# USB_UART.net
KiCad netlist of a schematic drawn in Altium Designer
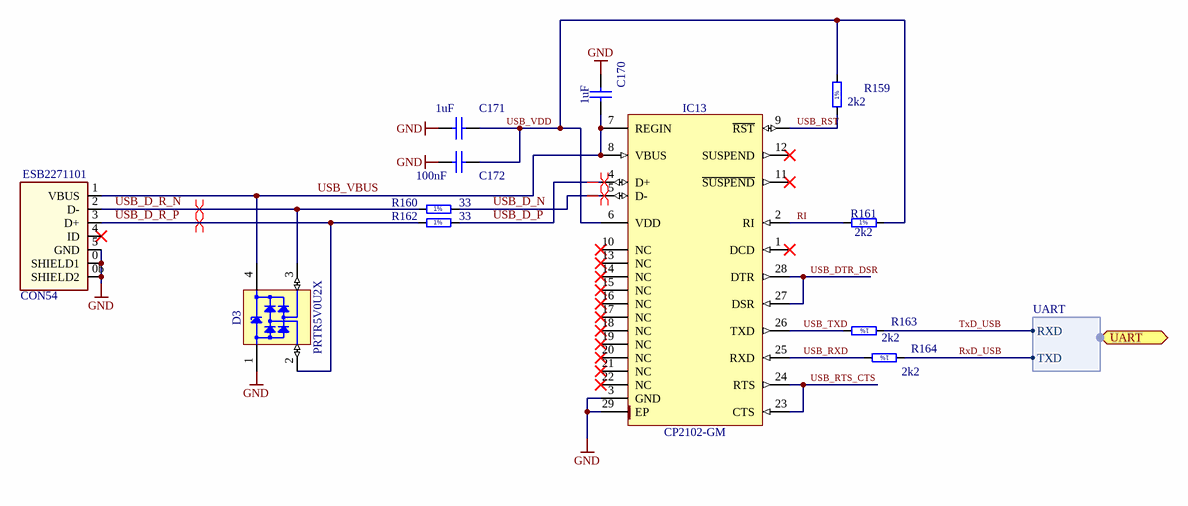
[diagram p0: USB_UART.SchDoc]

(export (version "E")
  (design (tool "Eeschema 10.0.6"))
  (components
    (comp (ref "C170")
      (value "1uF")
      (footprint "CAPC1608X87N")
      (description "Non-polarised capacitor")
      (fields
        (field (name "PART NUMBER") "CC0603_1UF_16V_10%_X7R")
        (field (name "VOLTAGE") "16V")
        (field (name "AUTHOR") "CERN DEM JLC")
      )
      (libsource (lib "Capacitors") (part "Capacitor - non polarized"))
    )
    (comp (ref "C171")
      (value "1uF")
      (footprint "CAPC1608X87N")
      (description "Non-polarised capacitor")
      (fields
        (field (name "PART NUMBER") "CC0603_1UF_16V_10%_X7R")
        (field (name "VOLTAGE") "16V")
        (field (name "AUTHOR") "CERN DEM JLC")
      )
      (libsource (lib "Capacitors") (part "Capacitor - non polarized"))
    )
    (comp (ref "C172")
      (value "100nF")
      (footprint "CAPC0603X33N")
      (description "Non-polarised capacitor")
      (fields
        (field (name "PART NUMBER") "CC0201_100NF_6.3V_10%_X5R")
        (field (name "VOLTAGE") "6.3V")
        (field (name "AUTHOR") "CERN DEM JLC")
      )
      (libsource (lib "Capacitors") (part "Capacitor - non polarized"))
    )
    (comp (ref "CON54")
      (value "ESB2271101")
      (footprint "USB_MICRO_ESB2271101")
      (description "USB micro AB connector")
      (fields (field (name "PART NUMBER") "10133"))
      (libsource (lib "LIBRARY_SCH") (part "CON_USB_AB_MICRO"))
    )
    (comp (ref "D3")
      (value "PRTR5V0U2X")
      (footprint "SOT190P230X110-4N")
      (description "Ultra Low Capacitance Double Rail-to-Rail ESD Protection Diode")
      (fields
        (field (name "VOLTAGE") "5.5V")
        (field (name "MANUFACTURER") "NXP SEMICONDUCTORS")
        (field (name "AUTHOR") "CERN DEM JLC")
      )
      (libsource (lib "ICs And Semiconductors") (part "PRTR5V0U2X"))
    )
    (comp (ref "IC13")
      (value "CP2102-GM")
      (footprint "QFN50P500X500X100-29N-S335")
      (description "Single-Chip USB to UART Bridge")
      (fields (field (name "MANUFACTURER") "SILICON LABS") (field (name "AUTHOR") "CERN DEM JLC"))
      (libsource (lib "ICs And Semiconductors") (part "CP2102-GM"))
    )
    (comp (ref "R159")
      (value "2k2")
      (footprint "RESC1005X40N")
      (description "Resistor - 1%")
      (fields
        (field (name "PART NUMBER") "R0402_2K2_1%_0.0625W_100PPM")
        (field (name "POWER") "0.0625W")
        (field (name "AUTHOR") "CERN DEM JLC")
      )
      (libsource (lib "Resistors") (part "Resistor - 1%"))
    )
    (comp (ref "R160")
      (value "33")
      (footprint "RESC1005X40N")
      (description "Resistor - 1%")
      (fields
        (field (name "PART NUMBER") "R0402_33R_1%_0.0625W_100PPM")
        (field (name "POWER") "0.0625W")
        (field (name "AUTHOR") "CERN DEM JLC")
      )
      (libsource (lib "Resistors") (part "Resistor - 1%"))
    )
    (comp (ref "R161")
      (value "2k2")
      (footprint "RESC1005X40N")
      (description "Resistor - 1%")
      (fields
        (field (name "PART NUMBER") "R0402_2K2_1%_0.0625W_100PPM")
        (field (name "POWER") "0.0625W")
        (field (name "AUTHOR") "CERN DEM JLC")
      )
      (libsource (lib "Resistors") (part "Resistor - 1%"))
    )
    (comp (ref "R162")
      (value "33")
      (footprint "RESC1005X40N")
      (description "Resistor - 1%")
      (fields
        (field (name "PART NUMBER") "R0402_33R_1%_0.0625W_100PPM")
        (field (name "POWER") "0.0625W")
        (field (name "AUTHOR") "CERN DEM JLC")
      )
      (libsource (lib "Resistors") (part "Resistor - 1%"))
    )
    (comp (ref "R163")
      (value "2k2")
      (footprint "RESC1005X40N")
      (description "Resistor - 1%")
      (fields
        (field (name "PART NUMBER") "R0402_2K2_1%_0.0625W_100PPM")
        (field (name "POWER") "0.0625W")
        (field (name "AUTHOR") "CERN DEM JLC")
      )
      (libsource (lib "Resistors") (part "Resistor - 1%"))
    )
    (comp (ref "R164")
      (value "2k2")
      (footprint "RESC1005X40N")
      (description "Resistor - 1%")
      (fields
        (field (name "PART NUMBER") "R0402_2K2_1%_0.0625W_100PPM")
        (field (name "POWER") "0.0625W")
        (field (name "AUTHOR") "CERN DEM JLC")
      )
      (libsource (lib "Resistors") (part "Resistor - 1%"))
    )
  )
  (nets
    (net (code "2") (name "/RI") (class "Default")
      (node (ref "IC13") (pin "2") (pinfunction "RI_2") (pintype "input"))
      (node (ref "R161") (pin "1") (pinfunction "1_1") (pintype "passive"))
    )
    (net (code "3") (name "/RxD_USB") (class "Default")
      (node (ref "R164") (pin "1") (pinfunction "1_1") (pintype "passive"))
    )
    (net (code "4") (name "/TxD_USB") (class "Default")
      (node (ref "R163") (pin "1") (pinfunction "1_1") (pintype "passive"))
    )
    (net (code "5") (name "/USB_DTR_DSR") (class "Default")
      (node (ref "IC13") (pin "27") (pinfunction "DSR_27") (pintype "input"))
      (node (ref "IC13") (pin "28") (pinfunction "DTR_28") (pintype "output"))
    )
    (net (code "6") (name "/USB_D_N") (class "Default")
      (node (ref "IC13") (pin "5") (pinfunction "D-_5") (pintype "bidirectional"))
      (node (ref "R160") (pin "2") (pinfunction "2_2") (pintype "passive"))
    )
    (net (code "7") (name "/USB_D_P") (class "Default")
      (node (ref "IC13") (pin "4") (pinfunction "D+_4") (pintype "bidirectional"))
      (node (ref "R162") (pin "2") (pinfunction "2_2") (pintype "passive"))
    )
    (net (code "8") (name "/USB_D_R_N") (class "Default")
      (node (ref "CON54") (pin "2") (pinfunction "D-_2") (pintype "passive"))
      (node (ref "D3") (pin "3") (pinfunction "I/O2_3") (pintype "bidirectional"))
      (node (ref "R160") (pin "1") (pinfunction "1_1") (pintype "passive"))
    )
    (net (code "9") (name "/USB_D_R_P") (class "Default")
      (node (ref "CON54") (pin "3") (pinfunction "D+_3") (pintype "passive"))
      (node (ref "D3") (pin "2") (pinfunction "I/O1_2") (pintype "bidirectional"))
      (node (ref "R162") (pin "1") (pinfunction "1_1") (pintype "passive"))
    )
    (net (code "10") (name "/USB_RST") (class "Default")
      (node (ref "IC13") (pin "9") (pinfunction "~{RST}_9") (pintype "bidirectional"))
      (node (ref "R159") (pin "1") (pinfunction "1_1") (pintype "passive"))
    )
    (net (code "11") (name "/USB_RTS_CTS") (class "Default")
      (node (ref "IC13") (pin "23") (pinfunction "CTS_23") (pintype "input"))
      (node (ref "IC13") (pin "24") (pinfunction "RTS_24") (pintype "output"))
    )
    (net (code "12") (name "/USB_RXD") (class "Default")
      (node (ref "IC13") (pin "25") (pinfunction "RXD_25") (pintype "input"))
      (node (ref "R164") (pin "2") (pinfunction "2_2") (pintype "passive"))
    )
    (net (code "13") (name "/USB_TXD") (class "Default")
      (node (ref "IC13") (pin "26") (pinfunction "TXD_26") (pintype "output"))
      (node (ref "R163") (pin "2") (pinfunction "2_2") (pintype "passive"))
    )
    (net (code "14") (name "/USB_VBUS") (class "Default")
      (node (ref "C170") (pin "2") (pinfunction "2_2") (pintype "passive"))
      (node (ref "CON54") (pin "1") (pinfunction "VBUS_1") (pintype "passive"))
      (node (ref "D3") (pin "4") (pinfunction "VCC_4") (pintype "power_in"))
      (node (ref "IC13") (pin "7") (pinfunction "REGIN_7") (pintype "power_in"))
      (node (ref "IC13") (pin "8") (pinfunction "VBUS_8") (pintype "input"))
    )
    (net (code "15") (name "/USB_VDD") (class "Default")
      (node (ref "C171") (pin "2") (pinfunction "2_2") (pintype "passive"))
      (node (ref "C172") (pin "2") (pinfunction "2_2") (pintype "passive"))
      (node (ref "IC13") (pin "6") (pinfunction "VDD_6") (pintype "power_in"))
      (node (ref "R159") (pin "2") (pinfunction "2_2") (pintype "passive"))
      (node (ref "R161") (pin "2") (pinfunction "2_2") (pintype "passive"))
    )
    (net (code "17") (name "GND") (class "Default")
      (node (ref "C170") (pin "1") (pinfunction "1_1") (pintype "passive"))
      (node (ref "C171") (pin "1") (pinfunction "1_1") (pintype "passive"))
      (node (ref "C172") (pin "1") (pinfunction "1_1") (pintype "passive"))
      (node (ref "CON54") (pin "0") (pinfunction "SHIELD1_0") (pintype "passive"))
      (node (ref "CON54") (pin "0a") (pinfunction "SHIELD1_0a") (pintype "passive"))
      (node (ref "CON54") (pin "0b") (pinfunction "SHIELD2_0b") (pintype "passive"))
      (node (ref "CON54") (pin "0c") (pinfunction "SHIELD2_0c") (pintype "passive"))
      (node (ref "CON54") (pin "5") (pinfunction "GND_5") (pintype "passive"))
      (node (ref "D3") (pin "1") (pinfunction "GND_1") (pintype "power_in"))
      (node (ref "IC13") (pin "29") (pinfunction "EP_29") (pintype "power_in"))
      (node (ref "IC13") (pin "3") (pinfunction "GND_3") (pintype "power_in"))
    )
    (net (code "18") (name "unconnected-(CON54-ID-Pad4)") (class "Default")
      (node (ref "CON54") (pin "4") (pinfunction "ID_4") (pintype "passive+no_connect"))
    )
    (net (code "19") (name "unconnected-(IC13-DCD-Pad1)") (class "Default")
      (node (ref "IC13") (pin "1") (pinfunction "DCD_1") (pintype "input+no_connect"))
    )
    (net (code "20") (name "unconnected-(IC13-NC-Pad10)") (class "Default")
      (node (ref "IC13") (pin "10") (pinfunction "NC_10") (pintype "passive+no_connect"))
    )
    (net (code "21") (name "unconnected-(IC13-NC-Pad13)") (class "Default")
      (node (ref "IC13") (pin "13") (pinfunction "NC_13") (pintype "passive+no_connect"))
    )
    (net (code "22") (name "unconnected-(IC13-NC-Pad14)") (class "Default")
      (node (ref "IC13") (pin "14") (pinfunction "NC_14") (pintype "passive+no_connect"))
    )
    (net (code "23") (name "unconnected-(IC13-NC-Pad15)") (class "Default")
      (node (ref "IC13") (pin "15") (pinfunction "NC_15") (pintype "passive+no_connect"))
    )
    (net (code "24") (name "unconnected-(IC13-NC-Pad16)") (class "Default")
      (node (ref "IC13") (pin "16") (pinfunction "NC_16") (pintype "passive+no_connect"))
    )
    (net (code "25") (name "unconnected-(IC13-NC-Pad17)") (class "Default")
      (node (ref "IC13") (pin "17") (pinfunction "NC_17") (pintype "passive+no_connect"))
    )
    (net (code "26") (name "unconnected-(IC13-NC-Pad18)") (class "Default")
      (node (ref "IC13") (pin "18") (pinfunction "NC_18") (pintype "passive+no_connect"))
    )
    (net (code "27") (name "unconnected-(IC13-NC-Pad19)") (class "Default")
      (node (ref "IC13") (pin "19") (pinfunction "NC_19") (pintype "passive+no_connect"))
    )
    (net (code "28") (name "unconnected-(IC13-NC-Pad20)") (class "Default")
      (node (ref "IC13") (pin "20") (pinfunction "NC_20") (pintype "passive+no_connect"))
    )
    (net (code "29") (name "unconnected-(IC13-NC-Pad21)") (class "Default")
      (node (ref "IC13") (pin "21") (pinfunction "NC_21") (pintype "passive+no_connect"))
    )
    (net (code "30") (name "unconnected-(IC13-NC-Pad22)") (class "Default")
      (node (ref "IC13") (pin "22") (pinfunction "NC_22") (pintype "passive+no_connect"))
    )
    (net (code "31") (name "unconnected-(IC13-SUSPEND-Pad12)") (class "Default")
      (node (ref "IC13") (pin "12") (pinfunction "SUSPEND_12") (pintype "output+no_connect"))
    )
    (net (code "32") (name "unconnected-(IC13-~{SUSPEND}-Pad11)") (class "Default")
      (node (ref "IC13") (pin "11") (pinfunction "~{SUSPEND}_11") (pintype "output+no_connect"))
    )
  )
)
